# Microcontroller.net
KiCad netlist of a schematic drawn in Altium Designer
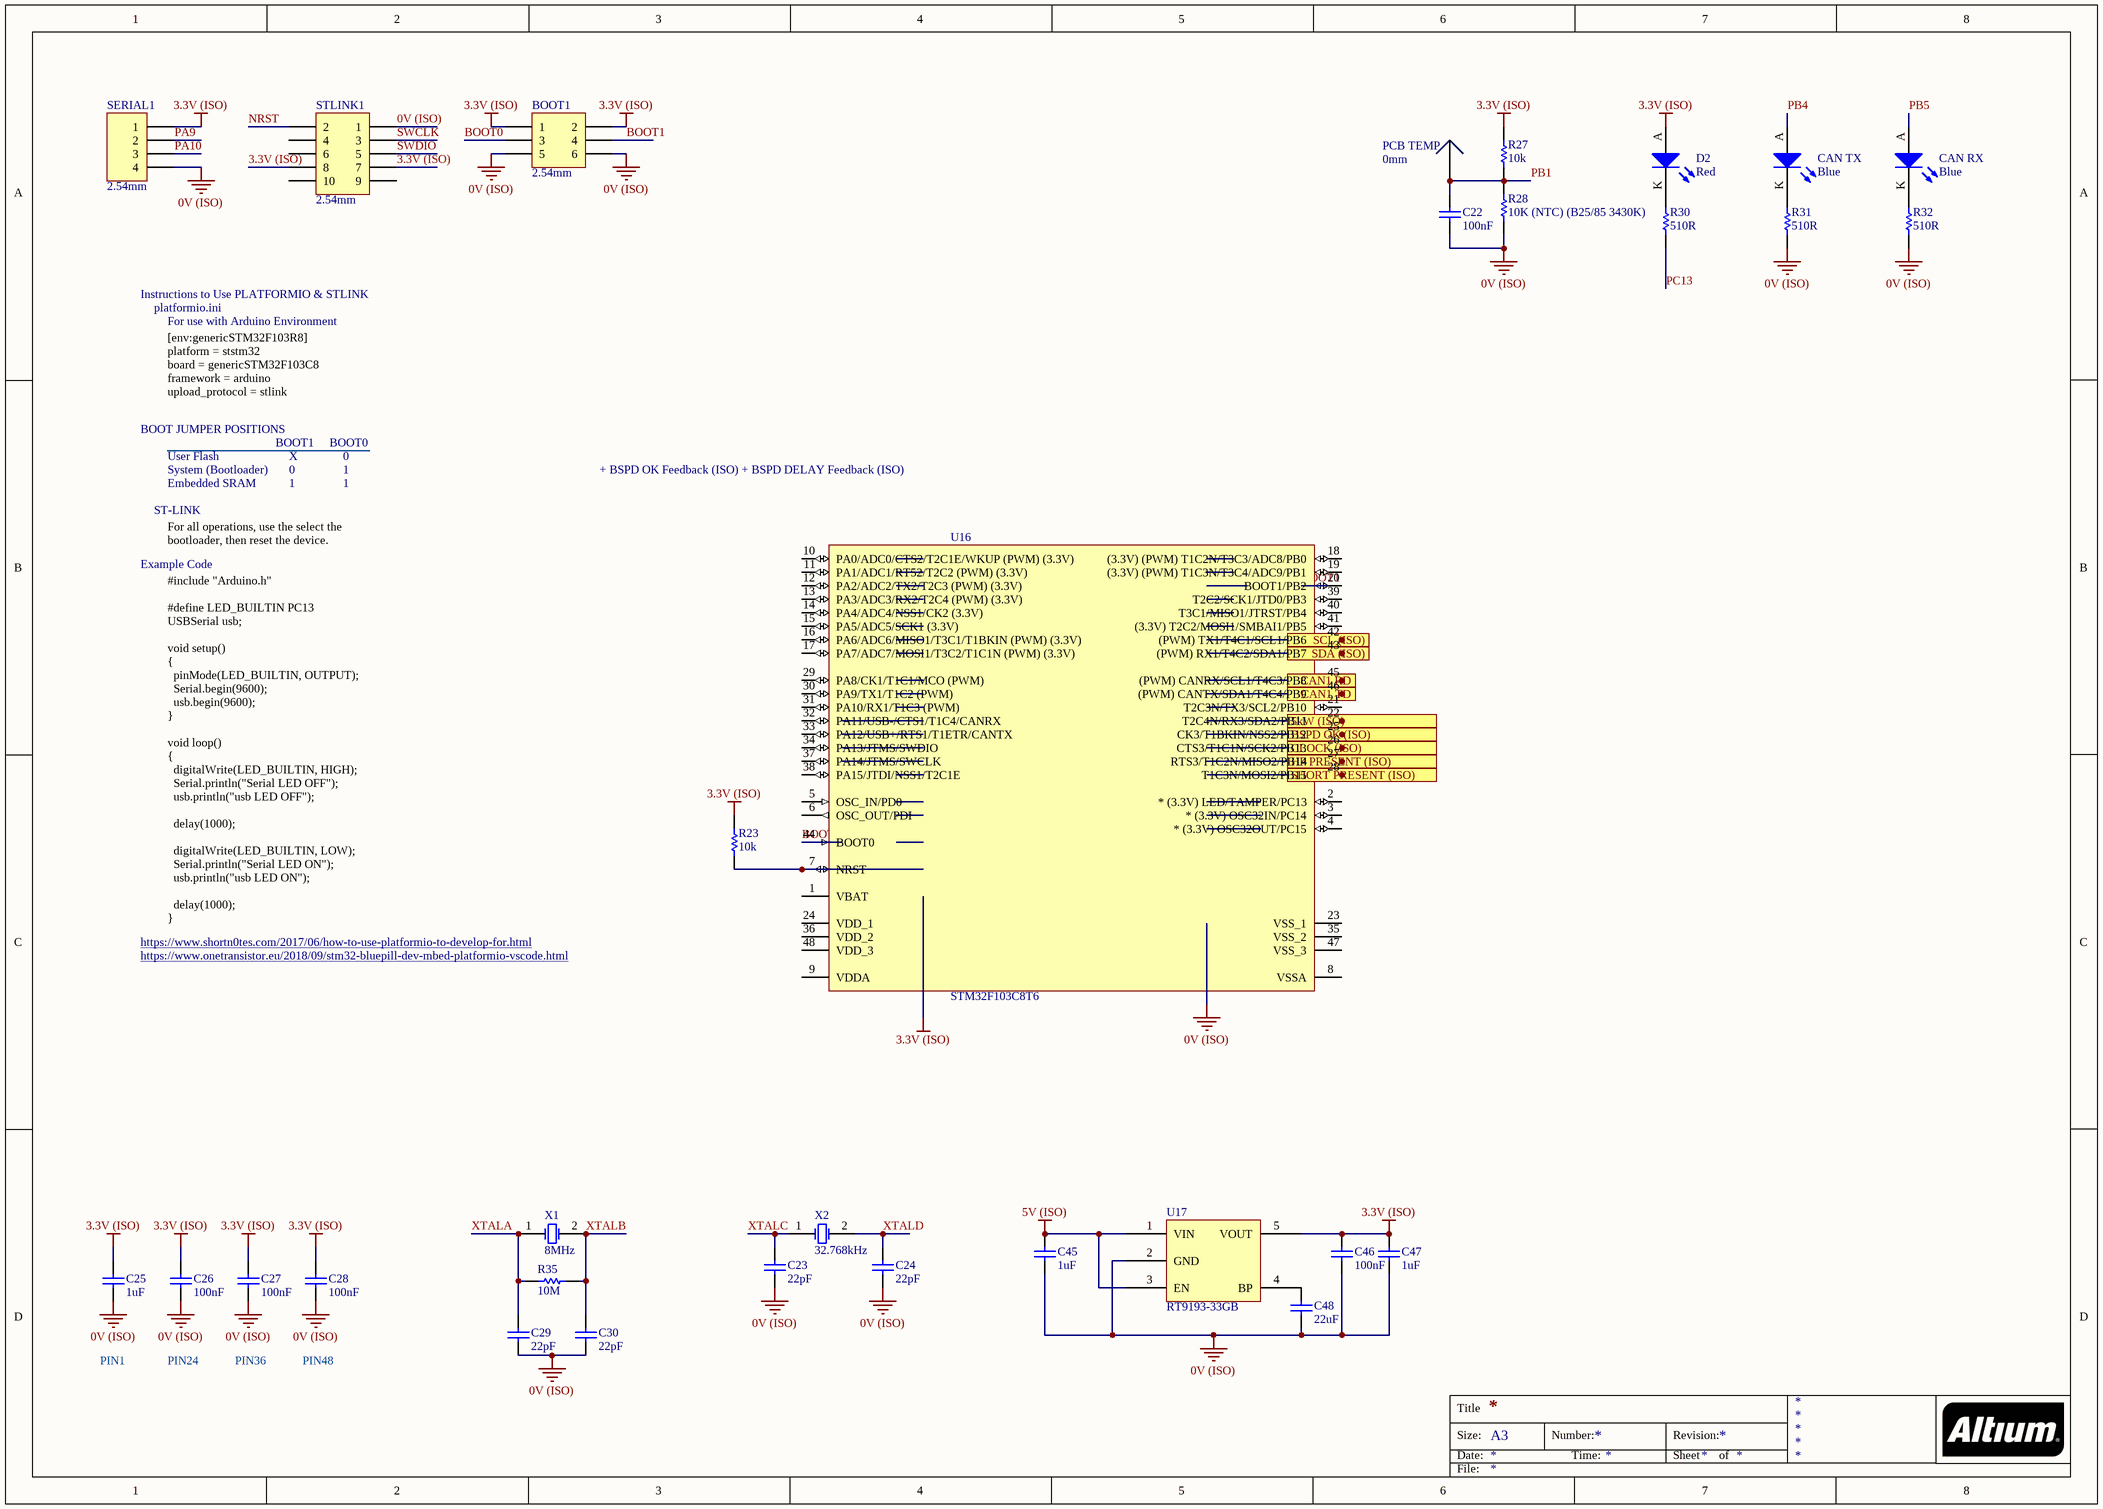
[diagram p0: Microcontroller.SchDoc]

(export (version "E")
  (design (tool "Eeschema 10.0.6"))
  (components
    (comp (ref "BOOT1")
      (value "2.54mm")
      (footprint "TH 2.54mm Header 2x3")
      (fields (field (name "PART NUMBER") "TH 2.54mm Header 2x3") (field (name "CONTACT") "NA"))
      (libsource (lib "ts_20-standard-connectors") (part "Header 2x3"))
    )
    (comp (ref "C22")
      (value "100nF")
      (footprint "0805")
      (fields
        (field (name "PART NUMBER") "GCM21BR71E104KA37L")
        (field (name "TOLERANCE") "10%")
        (field (name "MANUFACTURER") "muRata")
      )
      (libsource (lib "ts_20-standard-library") (part "Capacitor"))
    )
    (comp (ref "C23")
      (value "22pF")
      (footprint "0805")
      (fields
        (field (name "PART NUMBER") "GCM21B5C1H220JA37L")
        (field (name "TOLERANCE") "5%")
        (field (name "MANUFACTURER") "muRata")
      )
      (libsource (lib "ts_20-standard-library") (part "Capacitor"))
    )
    (comp (ref "C24")
      (value "22pF")
      (footprint "0805")
      (fields
        (field (name "PART NUMBER") "GCM21B5C1H220JA37L")
        (field (name "TOLERANCE") "5%")
        (field (name "MANUFACTURER") "muRata")
      )
      (libsource (lib "ts_20-standard-library") (part "Capacitor"))
    )
    (comp (ref "C25")
      (value "1uF")
      (footprint "0805")
      (fields
        (field (name "PART NUMBER") "AC0805KKX7R8BB105")
        (field (name "TOLERANCE") "10%")
        (field (name "MANUFACTURER") "YAGEO")
      )
      (libsource (lib "ts_20-standard-library") (part "Capacitor"))
    )
    (comp (ref "C26")
      (value "100nF")
      (footprint "0805")
      (fields
        (field (name "PART NUMBER") "GCM21BR71E104KA37L")
        (field (name "TOLERANCE") "10%")
        (field (name "MANUFACTURER") "muRata")
      )
      (libsource (lib "ts_20-standard-library") (part "Capacitor"))
    )
    (comp (ref "C27")
      (value "100nF")
      (footprint "0805")
      (fields
        (field (name "PART NUMBER") "GCM21BR71E104KA37L")
        (field (name "TOLERANCE") "10%")
        (field (name "MANUFACTURER") "muRata")
      )
      (libsource (lib "ts_20-standard-library") (part "Capacitor"))
    )
    (comp (ref "C28")
      (value "100nF")
      (footprint "0805")
      (fields
        (field (name "PART NUMBER") "GCM21BR71E104KA37L")
        (field (name "TOLERANCE") "10%")
        (field (name "MANUFACTURER") "muRata")
      )
      (libsource (lib "ts_20-standard-library") (part "Capacitor"))
    )
    (comp (ref "C29")
      (value "22pF")
      (footprint "0805")
      (fields
        (field (name "PART NUMBER") "GCM21B5C1H220JA37L")
        (field (name "TOLERANCE") "5%")
        (field (name "MANUFACTURER") "muRata")
      )
      (libsource (lib "ts_20-standard-library") (part "Capacitor"))
    )
    (comp (ref "C30")
      (value "22pF")
      (footprint "0805")
      (fields
        (field (name "PART NUMBER") "GCM21B5C1H220JA37L")
        (field (name "TOLERANCE") "5%")
        (field (name "MANUFACTURER") "muRata")
      )
      (libsource (lib "ts_20-standard-library") (part "Capacitor"))
    )
    (comp (ref "C45")
      (value "1uF")
      (footprint "0805")
      (fields
        (field (name "PART NUMBER") "GCM21BR71A105KA37L")
        (field (name "TOLERANCE") "10%")
        (field (name "MANUFACTURER") "muRata")
      )
      (libsource (lib "ts_20-standard-library") (part "Capacitor"))
    )
    (comp (ref "C46")
      (value "100nF")
      (footprint "0805")
      (fields
        (field (name "PART NUMBER") "GCM21BR71E104KA37L")
        (field (name "TOLERANCE") "10%")
        (field (name "MANUFACTURER") "muRata")
      )
      (libsource (lib "ts_20-standard-library") (part "Capacitor"))
    )
    (comp (ref "C47")
      (value "1uF")
      (footprint "0805")
      (fields
        (field (name "PART NUMBER") "GCM21BR71A105KA37L")
        (field (name "TOLERANCE") "10%")
        (field (name "MANUFACTURER") "muRata")
      )
      (libsource (lib "ts_20-standard-library") (part "Capacitor"))
    )
    (comp (ref "C48")
      (value "22uF")
      (footprint "0805")
      (fields
        (field (name "PART NUMBER") "GRM21BR61A226ME51L")
        (field (name "TOLERANCE") "20%")
        (field (name "MANUFACTURER") "muRata")
      )
      (libsource (lib "ts_20-standard-library") (part "Capacitor"))
    )
    (comp (ref "CAN RX")
      (value "Blue")
      (footprint "0805 LED")
      (description "LED BLUE CLEAR 2012 SMD")
      (fields
        (field (name "PART NUMBER") "SML-MN2BCTT86C")
        (field (name "MANUFACTURER") "ROHM Semiconductor")
      )
      (libsource (lib "ts_20-standard-library") (part "LED"))
    )
    (comp (ref "CAN TX")
      (value "Blue")
      (footprint "0805 LED")
      (description "LED BLUE CLEAR 2012 SMD")
      (fields
        (field (name "PART NUMBER") "SML-MN2BCTT86C")
        (field (name "MANUFACTURER") "ROHM Semiconductor")
      )
      (libsource (lib "ts_20-standard-library") (part "LED"))
    )
    (comp (ref "D2")
      (value "Red")
      (footprint "0805 LED")
      (description "Red LED Indication - Discrete 1.75V 0805 (2012 Metric)")
      (fields (field (name "PART NUMBER") "SML-210LTT86") (field (name "MANUFACTURER") "ROHM Semiconductor"))
      (libsource (lib "ts_20-standard-library") (part "LED"))
    )
    (comp (ref "PCB TEMP")
      (value "0mm")
      (footprint "SMD Test Point")
      (fields (field (name "PART NUMBER") "SMD Test Point") (field (name "CONTACT") "NA"))
      (libsource (lib "ts_20-standard-connectors") (part "Test Point"))
    )
    (comp (ref "R23")
      (value "10k")
      (footprint "0805")
      (fields
        (field (name "MANUFACTURER") "YAGEO")
        (field (name "PART NUMBER") "RC0805FR0710KL")
        (field (name "TOLERANCE") "0.01")
      )
      (libsource (lib "ts_20-standard-library") (part "Resistor"))
    )
    (comp (ref "R27")
      (value "10k")
      (footprint "0805")
      (fields
        (field (name "PART NUMBER") "RC0805FR0710KL")
        (field (name "MANUFACTURER") "YAGEO")
        (field (name "TOLERANCE") "0.01")
      )
      (libsource (lib "ts_20-standard-library") (part "Resistor"))
    )
    (comp (ref "R28")
      (value "10K (NTC) (B25/85 3430K)")
      (footprint "0805")
      (fields
        (field (name "PART NUMBER") "NTCS0805E3103FLT")
        (field (name "MANUFACTURER") "Vishay Beyschlag")
        (field (name "TOLERANCE") "0.01")
      )
      (libsource (lib "ts_20-standard-library") (part "Resistor"))
    )
    (comp (ref "R30")
      (value "510R")
      (footprint "0805")
      (fields
        (field (name "PART NUMBER") "RC0805FR07510RL")
        (field (name "MANUFACTURER") "YAGEO")
        (field (name "TOLERANCE") "0.01")
      )
      (libsource (lib "ts_20-standard-library") (part "Resistor"))
    )
    (comp (ref "R31")
      (value "510R")
      (footprint "0805")
      (fields
        (field (name "PART NUMBER") "RC0805FR07510RL")
        (field (name "MANUFACTURER") "YAGEO")
        (field (name "TOLERANCE") "0.01")
      )
      (libsource (lib "ts_20-standard-library") (part "Resistor"))
    )
    (comp (ref "R32")
      (value "510R")
      (footprint "0805")
      (fields
        (field (name "PART NUMBER") "RC0805FR07510RL")
        (field (name "MANUFACTURER") "YAGEO")
        (field (name "TOLERANCE") "0.01")
      )
      (libsource (lib "ts_20-standard-library") (part "Resistor"))
    )
    (comp (ref "R33")
      (value "10k")
      (footprint "0805")
      (fields
        (field (name "PART NUMBER") "RC0805FR0710KL")
        (field (name "MANUFACTURER") "YAGEO")
        (field (name "TOLERANCE") "0.01")
      )
      (libsource (lib "ts_20-standard-library") (part "Resistor"))
    )
    (comp (ref "R34")
      (value "10k")
      (footprint "0805")
      (fields
        (field (name "PART NUMBER") "RC0805FR0710KL")
        (field (name "MANUFACTURER") "YAGEO")
        (field (name "TOLERANCE") "0.01")
      )
      (libsource (lib "ts_20-standard-library") (part "Resistor"))
    )
    (comp (ref "R35")
      (value "10M")
      (footprint "0805")
      (fields
        (field (name "PART NUMBER") "RC0805FR0710ML")
        (field (name "MANUFACTURER") "YAGEO")
        (field (name "TOLERANCE") "0.01")
      )
      (libsource (lib "ts_20-standard-library") (part "Resistor"))
    )
    (comp (ref "SERIAL1")
      (value "2.54mm")
      (footprint "TH 2.54mm Header 1x4")
      (fields (field (name "PART NUMBER") "TH 2.54mm Header 1x4") (field (name "CONTACT") "NA"))
      (libsource (lib "ts_20-standard-connectors") (part "Header 1x4"))
    )
    (comp (ref "STLINK1")
      (value "2.54mm")
      (footprint "TH 2.54mm Header 2x5")
      (fields (field (name "PART NUMBER") "TH 2.54mm Header 2x5") (field (name "CONTACT") "NA"))
      (libsource (lib "ts_20-standard-connectors") (part "Header 2x5"))
    )
    (comp (ref "U16")
      (value "STM32F103C8T6")
      (footprint "STM 48-LQFP")
      (description "ARM® Cortex®-M3 STM32F1 Microcontroller IC 32-Bit 72MHz 64KB (64K x 8) FLASH")
      (fields
        (field (name "MANUFACTURER") "STMicroelectronics")
        (field (name "DIGIKEY PART NUMBER") "497-6063-ND")
      )
      (libsource (lib "ts_20-standard-library") (part "STM32F103C8T6"))
    )
    (comp (ref "U17")
      (value "RT9193-33GB")
      (footprint "RICHTEK SOT-23-5")
      (description "IC REG LINEAR 3.3V 300MA SOT23-5")
      (fields (field (name "MANUFACTURER") "Richtek") (field (name "DIGIKEY PART NUMBER") "1028-1014-1-ND"))
      (libsource (lib "ts_20-standard-library") (part "RT9193-33GB"))
    )
    (comp (ref "X1")
      (value "8MHz")
      (footprint "Abracon HC-49/US")
      (fields
        (field (name "PART NUMBER") "ABLS-8.000MHZ-B4-T")
        (field (name "MANUFACTURER") "Abracon LLC")
        (field (name "DIGIKEY PART NUMBER") "535-10212-2-ND")
      )
      (libsource (lib "ts_20-standard-library") (part "Crystal"))
    )
    (comp (ref "X2")
      (value "32.768kHz")
      (footprint "EPSON 2-SMD")
      (fields
        (field (name "PART NUMBER") "FC-135 32.7680KA-A5")
        (field (name "MANUFACTURER") "EPSON")
        (field (name "DIGIKEY PART NUMBER") "SER4103TR-ND")
      )
      (libsource (lib "ts_20-standard-library") (part "Crystal"))
    )
  )
  (nets
    (net (code "1") (name "/BOOT0") (class "Default")
      (node (ref "BOOT1") (pin "3") (pinfunction "3_3") (pintype "passive"))
      (node (ref "R34") (pin "1") (pinfunction "1_1") (pintype "passive"))
      (node (ref "U16") (pin "44") (pinfunction "BOOT0_44") (pintype "input"))
    )
    (net (code "2") (name "/BOOT1") (class "Default")
      (node (ref "BOOT1") (pin "4") (pinfunction "4_4") (pintype "passive"))
      (node (ref "R33") (pin "2") (pinfunction "2_2") (pintype "passive"))
    )
    (net (code "3") (name "/NRST") (class "Default")
      (node (ref "R23") (pin "1") (pinfunction "1_1") (pintype "passive"))
      (node (ref "STLINK1") (pin "2") (pinfunction "2_2") (pintype "passive"))
      (node (ref "U16") (pin "7") (pinfunction "NRST_7") (pintype "bidirectional"))
    )
    (net (code "13") (name "/PA9") (class "Default")
      (node (ref "SERIAL1") (pin "2") (pinfunction "2_2") (pintype "passive"))
    )
    (net (code "14") (name "/PA10") (class "Default")
      (node (ref "SERIAL1") (pin "3") (pinfunction "3_3") (pintype "passive"))
    )
    (net (code "17") (name "/PB1") (class "Default")
      (node (ref "C22") (pin "2") (pinfunction "2_2") (pintype "passive"))
      (node (ref "PCB TEMP") (pin "1") (pinfunction "1_1") (pintype "passive"))
      (node (ref "R27") (pin "1") (pinfunction "1_1") (pintype "passive"))
      (node (ref "R28") (pin "2") (pinfunction "2_2") (pintype "passive"))
    )
    (net (code "19") (name "/PB4") (class "Default")
      (node (ref "CAN TX") (pin "A") (pinfunction "A_A") (pintype "passive"))
    )
    (net (code "20") (name "/PB5") (class "Default")
      (node (ref "CAN RX") (pin "A") (pinfunction "A_A") (pintype "passive"))
    )
    (net (code "31") (name "/PC13") (class "Default")
      (node (ref "R30") (pin "1") (pinfunction "1_1") (pintype "passive"))
    )
    (net (code "32") (name "/SWCLK") (class "Default")
      (node (ref "STLINK1") (pin "3") (pinfunction "3_3") (pintype "passive"))
    )
    (net (code "33") (name "/SWDIO") (class "Default")
      (node (ref "STLINK1") (pin "5") (pinfunction "5_5") (pintype "passive"))
    )
    (net (code "36") (name "/XTALA") (class "Default")
      (node (ref "C29") (pin "2") (pinfunction "2_2") (pintype "passive"))
      (node (ref "R35") (pin "1") (pinfunction "1_1") (pintype "passive"))
      (node (ref "X1") (pin "1") (pinfunction "OSC1_1") (pintype "passive"))
    )
    (net (code "37") (name "/XTALB") (class "Default")
      (node (ref "C30") (pin "2") (pinfunction "2_2") (pintype "passive"))
      (node (ref "R35") (pin "2") (pinfunction "2_2") (pintype "passive"))
      (node (ref "X1") (pin "2") (pinfunction "OSC2_2") (pintype "passive"))
    )
    (net (code "38") (name "/XTALC") (class "Default")
      (node (ref "C23") (pin "2") (pinfunction "2_2") (pintype "passive"))
      (node (ref "X2") (pin "1") (pinfunction "OSC1_1") (pintype "passive"))
    )
    (net (code "39") (name "/XTALD") (class "Default")
      (node (ref "C24") (pin "2") (pinfunction "2_2") (pintype "passive"))
      (node (ref "X2") (pin "2") (pinfunction "OSC2_2") (pintype "passive"))
    )
    (net (code "40") (name "0V (ISO)") (class "Default")
      (node (ref "BOOT1") (pin "5") (pinfunction "5_5") (pintype "passive"))
      (node (ref "BOOT1") (pin "6") (pinfunction "6_6") (pintype "passive"))
      (node (ref "C22") (pin "1") (pinfunction "1_1") (pintype "passive"))
      (node (ref "C23") (pin "1") (pinfunction "1_1") (pintype "passive"))
      (node (ref "C24") (pin "1") (pinfunction "1_1") (pintype "passive"))
      (node (ref "C25") (pin "1") (pinfunction "1_1") (pintype "passive"))
      (node (ref "C26") (pin "1") (pinfunction "1_1") (pintype "passive"))
      (node (ref "C27") (pin "1") (pinfunction "1_1") (pintype "passive"))
      (node (ref "C28") (pin "1") (pinfunction "1_1") (pintype "passive"))
      (node (ref "C29") (pin "1") (pinfunction "1_1") (pintype "passive"))
      (node (ref "C30") (pin "1") (pinfunction "1_1") (pintype "passive"))
      (node (ref "C45") (pin "1") (pinfunction "1_1") (pintype "passive"))
      (node (ref "C46") (pin "1") (pinfunction "1_1") (pintype "passive"))
      (node (ref "C47") (pin "1") (pinfunction "1_1") (pintype "passive"))
      (node (ref "C48") (pin "1") (pinfunction "1_1") (pintype "passive"))
      (node (ref "R28") (pin "1") (pinfunction "1_1") (pintype "passive"))
      (node (ref "R31") (pin "1") (pinfunction "1_1") (pintype "passive"))
      (node (ref "R32") (pin "1") (pinfunction "1_1") (pintype "passive"))
      (node (ref "SERIAL1") (pin "4") (pinfunction "4_4") (pintype "passive"))
      (node (ref "STLINK1") (pin "1") (pinfunction "1_1") (pintype "passive"))
      (node (ref "U17") (pin "2") (pinfunction "GND_2") (pintype "passive"))
    )
    (net (code "41") (name "3.3V (ISO)") (class "Default")
      (node (ref "BOOT1") (pin "1") (pinfunction "1_1") (pintype "passive"))
      (node (ref "BOOT1") (pin "2") (pinfunction "2_2") (pintype "passive"))
      (node (ref "C25") (pin "2") (pinfunction "2_2") (pintype "passive"))
      (node (ref "C26") (pin "2") (pinfunction "2_2") (pintype "passive"))
      (node (ref "C27") (pin "2") (pinfunction "2_2") (pintype "passive"))
      (node (ref "C28") (pin "2") (pinfunction "2_2") (pintype "passive"))
      (node (ref "C46") (pin "2") (pinfunction "2_2") (pintype "passive"))
      (node (ref "C47") (pin "2") (pinfunction "2_2") (pintype "passive"))
      (node (ref "D2") (pin "A") (pinfunction "A_A") (pintype "passive"))
      (node (ref "R23") (pin "2") (pinfunction "2_2") (pintype "passive"))
      (node (ref "R27") (pin "2") (pinfunction "2_2") (pintype "passive"))
      (node (ref "SERIAL1") (pin "1") (pinfunction "1_1") (pintype "passive"))
      (node (ref "STLINK1") (pin "7") (pinfunction "7_7") (pintype "passive"))
      (node (ref "STLINK1") (pin "8") (pinfunction "8_8") (pintype "passive"))
      (node (ref "U17") (pin "5") (pinfunction "VOUT_5") (pintype "passive"))
    )
    (net (code "42") (name "5V (ISO)") (class "Default")
      (node (ref "C45") (pin "2") (pinfunction "2_2") (pintype "passive"))
      (node (ref "U17") (pin "1") (pinfunction "VIN_1") (pintype "passive"))
      (node (ref "U17") (pin "3") (pinfunction "EN_3") (pintype "passive"))
    )
    (net (code "43") (name "Net-(CAN RX-PadK)") (class "Default")
      (node (ref "CAN RX") (pin "K") (pinfunction "K_K") (pintype "passive"))
      (node (ref "R32") (pin "2") (pinfunction "2_2") (pintype "passive"))
    )
    (net (code "44") (name "Net-(CAN TX-PadK)") (class "Default")
      (node (ref "CAN TX") (pin "K") (pinfunction "K_K") (pintype "passive"))
      (node (ref "R31") (pin "2") (pinfunction "2_2") (pintype "passive"))
    )
    (net (code "45") (name "Net-(D2-PadK)") (class "Default")
      (node (ref "D2") (pin "K") (pinfunction "K_K") (pintype "passive"))
      (node (ref "R30") (pin "2") (pinfunction "2_2") (pintype "passive"))
    )
    (net (code "46") (name "Net-(U17-BP)") (class "Default")
      (node (ref "C48") (pin "2") (pinfunction "2_2") (pintype "passive"))
      (node (ref "U17") (pin "4") (pinfunction "BP_4") (pintype "passive"))
    )
    (net (code "47") (name "unconnected-(R33-Pad1)") (class "Default")
      (node (ref "R33") (pin "1") (pinfunction "1_1") (pintype "passive"))
    )
    (net (code "48") (name "unconnected-(R34-Pad2)") (class "Default")
      (node (ref "R34") (pin "2") (pinfunction "2_2") (pintype "passive"))
    )
    (net (code "49") (name "unconnected-(STLINK1-Pad4)") (class "Default")
      (node (ref "STLINK1") (pin "4") (pinfunction "4_4") (pintype "passive"))
    )
    (net (code "50") (name "unconnected-(STLINK1-Pad6)") (class "Default")
      (node (ref "STLINK1") (pin "6") (pinfunction "6_6") (pintype "passive"))
    )
    (net (code "51") (name "unconnected-(STLINK1-Pad9)") (class "Default")
      (node (ref "STLINK1") (pin "9") (pinfunction "9_9") (pintype "passive"))
    )
    (net (code "52") (name "unconnected-(STLINK1-Pad10)") (class "Default")
      (node (ref "STLINK1") (pin "10") (pinfunction "10_10") (pintype "passive"))
    )
    (net (code "53") (name "unconnected-(U16-(3.3V)_(PWM)_T1C2N{slash}T3C3{slash}ADC8{slash}PB0-Pad18)") (class "Default")
      (node (ref "U16") (pin "18") (pinfunction "(3.3V)_(PWM)_T1C2N/T3C3/ADC8/PB0_18") (pintype "bidirectional"))
    )
    (net (code "54") (name "unconnected-(U16-(3.3V)_(PWM)_T1C3N{slash}T3C4{slash}ADC9{slash}PB1-Pad19)") (class "Default")
      (node (ref "U16") (pin "19") (pinfunction "(3.3V)_(PWM)_T1C3N/T3C4/ADC9/PB1_19") (pintype "bidirectional"))
    )
    (net (code "55") (name "unconnected-(U16-(3.3V)_T2C2{slash}MOSI1{slash}SMBAI1{slash}PB5-Pad41)") (class "Default")
      (node (ref "U16") (pin "41") (pinfunction "(3.3V)_T2C2/MOSI1/SMBAI1/PB5_41") (pintype "bidirectional"))
    )
    (net (code "56") (name "unconnected-(U16-(PWM)_CANRX{slash}SCL1{slash}T4C3{slash}PB8-Pad45)") (class "Default")
      (node (ref "U16") (pin "45") (pinfunction "(PWM)_CANRX/SCL1/T4C3/PB8_45") (pintype "bidirectional"))
    )
    (net (code "57") (name "unconnected-(U16-(PWM)_CANTX{slash}SDA1{slash}T4C4{slash}PB9-Pad46)") (class "Default")
      (node (ref "U16") (pin "46") (pinfunction "(PWM)_CANTX/SDA1/T4C4/PB9_46") (pintype "bidirectional"))
    )
    (net (code "58") (name "unconnected-(U16-(PWM)_RX1{slash}T4C2{slash}SDA1{slash}PB7-Pad43)") (class "Default")
      (node (ref "U16") (pin "43") (pinfunction "(PWM)_RX1/T4C2/SDA1/PB7_43") (pintype "bidirectional"))
    )
    (net (code "59") (name "unconnected-(U16-(PWM)_TX1{slash}T4C1{slash}SCL1{slash}PB6-Pad42)") (class "Default")
      (node (ref "U16") (pin "42") (pinfunction "(PWM)_TX1/T4C1/SCL1/PB6_42") (pintype "bidirectional"))
    )
    (net (code "60") (name "unconnected-(U16-*_(3.3V)_LED{slash}TAMPER{slash}PC13-Pad2)") (class "Default")
      (node (ref "U16") (pin "2") (pinfunction "*_(3.3V)_LED/TAMPER/PC13_2") (pintype "bidirectional"))
    )
    (net (code "61") (name "unconnected-(U16-*_(3.3V)_OSC32IN{slash}PC14-Pad3)") (class "Default")
      (node (ref "U16") (pin "3") (pinfunction "*_(3.3V)_OSC32IN/PC14_3") (pintype "bidirectional"))
    )
    (net (code "62") (name "unconnected-(U16-*_(3.3V)_OSC32OUT{slash}PC15-Pad4)") (class "Default")
      (node (ref "U16") (pin "4") (pinfunction "*_(3.3V)_OSC32OUT/PC15_4") (pintype "bidirectional"))
    )
    (net (code "63") (name "unconnected-(U16-BOOT1{slash}PB2-Pad20)") (class "Default")
      (node (ref "U16") (pin "20") (pinfunction "BOOT1/PB2_20") (pintype "bidirectional"))
    )
    (net (code "64") (name "unconnected-(U16-CK3{slash}T1BKIN{slash}NSS2{slash}PB12-Pad25)") (class "Default")
      (node (ref "U16") (pin "25") (pinfunction "CK3/T1BKIN/NSS2/PB12_25") (pintype "bidirectional"))
    )
    (net (code "65") (name "unconnected-(U16-CTS3{slash}T1C1N{slash}SCK2{slash}PB13-Pad26)") (class "Default")
      (node (ref "U16") (pin "26") (pinfunction "CTS3/T1C1N/SCK2/PB13_26") (pintype "bidirectional"))
    )
    (net (code "66") (name "unconnected-(U16-OSC_IN{slash}PD0-Pad5)") (class "Default")
      (node (ref "U16") (pin "5") (pinfunction "OSC_IN/PD0_5") (pintype "input"))
    )
    (net (code "67") (name "unconnected-(U16-OSC_OUT{slash}PDI-Pad6)") (class "Default")
      (node (ref "U16") (pin "6") (pinfunction "OSC_OUT/PDI_6") (pintype "output"))
    )
    (net (code "68") (name "unconnected-(U16-PA0{slash}ADC0{slash}CTS2{slash}T2C1E{slash}WKUP_(PWM)_(3.3V)-Pad10)") (class "Default")
      (node (ref "U16") (pin "10") (pinfunction "PA0/ADC0/CTS2/T2C1E/WKUP_(PWM)_(3.3V)_10") (pintype "bidirectional"))
    )
    (net (code "69") (name "unconnected-(U16-PA1{slash}ADC1{slash}RT52{slash}T2C2_(PWM)_(3.3V)-Pad11)") (class "Default")
      (node (ref "U16") (pin "11") (pinfunction "PA1/ADC1/RT52/T2C2_(PWM)_(3.3V)_11") (pintype "bidirectional"))
    )
    (net (code "70") (name "unconnected-(U16-PA2{slash}ADC2{slash}TX2{slash}T2C3_(PWM)_(3.3V)-Pad12)") (class "Default")
      (node (ref "U16") (pin "12") (pinfunction "PA2/ADC2/TX2/T2C3_(PWM)_(3.3V)_12") (pintype "bidirectional"))
    )
    (net (code "71") (name "unconnected-(U16-PA3{slash}ADC3{slash}RX2{slash}T2C4_(PWM)_(3.3V)-Pad13)") (class "Default")
      (node (ref "U16") (pin "13") (pinfunction "PA3/ADC3/RX2/T2C4_(PWM)_(3.3V)_13") (pintype "bidirectional"))
    )
    (net (code "72") (name "unconnected-(U16-PA4{slash}ADC4{slash}NSS1{slash}CK2_(3.3V)-Pad14)") (class "Default")
      (node (ref "U16") (pin "14") (pinfunction "PA4/ADC4/NSS1/CK2_(3.3V)_14") (pintype "bidirectional"))
    )
    (net (code "73") (name "unconnected-(U16-PA5{slash}ADC5{slash}SCK1_(3.3V)-Pad15)") (class "Default")
      (node (ref "U16") (pin "15") (pinfunction "PA5/ADC5/SCK1_(3.3V)_15") (pintype "bidirectional"))
    )
    (net (code "74") (name "unconnected-(U16-PA6{slash}ADC6{slash}MISO1{slash}T3C1{slash}T1BKIN_(PWM)_(3.3V)-Pad16)") (class "Default")
      (node (ref "U16") (pin "16") (pinfunction "PA6/ADC6/MISO1/T3C1/T1BKIN_(PWM)_(3.3V)_16") (pintype "bidirectional"))
    )
    (net (code "75") (name "unconnected-(U16-PA7{slash}ADC7{slash}MOSI1{slash}T3C2{slash}T1C1N_(PWM)_(3.3V)-Pad17)") (class "Default")
      (node (ref "U16") (pin "17") (pinfunction "PA7/ADC7/MOSI1/T3C2/T1C1N_(PWM)_(3.3V)_17") (pintype "bidirectional"))
    )
    (net (code "76") (name "unconnected-(U16-PA8{slash}CK1{slash}T1C1{slash}MCO_(PWM)-Pad29)") (class "Default")
      (node (ref "U16") (pin "29") (pinfunction "PA8/CK1/T1C1/MCO_(PWM)_29") (pintype "bidirectional"))
    )
    (net (code "77") (name "unconnected-(U16-PA9{slash}TX1{slash}T1C2_(PWM)-Pad30)") (class "Default")
      (node (ref "U16") (pin "30") (pinfunction "PA9/TX1/T1C2_(PWM)_30") (pintype "bidirectional"))
    )
    (net (code "78") (name "unconnected-(U16-PA10{slash}RX1{slash}T1C3_(PWM)-Pad31)") (class "Default")
      (node (ref "U16") (pin "31") (pinfunction "PA10/RX1/T1C3_(PWM)_31") (pintype "bidirectional"))
    )
    (net (code "79") (name "unconnected-(U16-PA11{slash}USB-{slash}CTS1{slash}T1C4{slash}CANRX-Pad32)") (class "Default")
      (node (ref "U16") (pin "32") (pinfunction "PA11/USB-/CTS1/T1C4/CANRX_32") (pintype "bidirectional"))
    )
    (net (code "80") (name "unconnected-(U16-PA12{slash}USB+{slash}RTS1{slash}T1ETR{slash}CANTX-Pad33)") (class "Default")
      (node (ref "U16") (pin "33") (pinfunction "PA12/USB+/RTS1/T1ETR/CANTX_33") (pintype "bidirectional"))
    )
    (net (code "81") (name "unconnected-(U16-PA13{slash}JTMS{slash}SWDIO-Pad34)") (class "Default")
      (node (ref "U16") (pin "34") (pinfunction "PA13/JTMS/SWDIO_34") (pintype "bidirectional"))
    )
    (net (code "82") (name "unconnected-(U16-PA14{slash}JTMS{slash}SWCLK-Pad37)") (class "Default")
      (node (ref "U16") (pin "37") (pinfunction "PA14/JTMS/SWCLK_37") (pintype "bidirectional"))
    )
    (net (code "83") (name "unconnected-(U16-PA15{slash}JTDI{slash}NSS1{slash}T2C1E-Pad38)") (class "Default")
      (node (ref "U16") (pin "38") (pinfunction "PA15/JTDI/NSS1/T2C1E_38") (pintype "bidirectional"))
    )
    (net (code "84") (name "unconnected-(U16-RTS3{slash}T1C2N{slash}MISO2{slash}PB14-Pad27)") (class "Default")
      (node (ref "U16") (pin "27") (pinfunction "RTS3/T1C2N/MISO2/PB14_27") (pintype "bidirectional"))
    )
    (net (code "85") (name "unconnected-(U16-T1C3N{slash}MOSI2{slash}PB15-Pad28)") (class "Default")
      (node (ref "U16") (pin "28") (pinfunction "T1C3N/MOSI2/PB15_28") (pintype "bidirectional"))
    )
    (net (code "86") (name "unconnected-(U16-T2C2{slash}SCK1{slash}JTD0{slash}PB3-Pad39)") (class "Default")
      (node (ref "U16") (pin "39") (pinfunction "T2C2/SCK1/JTD0/PB3_39") (pintype "bidirectional"))
    )
    (net (code "87") (name "unconnected-(U16-T2C3N{slash}TX3{slash}SCL2{slash}PB10-Pad21)") (class "Default")
      (node (ref "U16") (pin "21") (pinfunction "T2C3N/TX3/SCL2/PB10_21") (pintype "bidirectional"))
    )
    (net (code "88") (name "unconnected-(U16-T2C4N{slash}RX3{slash}SDA2{slash}PB11-Pad22)") (class "Default")
      (node (ref "U16") (pin "22") (pinfunction "T2C4N/RX3/SDA2/PB11_22") (pintype "bidirectional"))
    )
    (net (code "89") (name "unconnected-(U16-T3C1{slash}MISO1{slash}JTRST{slash}PB4-Pad40)") (class "Default")
      (node (ref "U16") (pin "40") (pinfunction "T3C1/MISO1/JTRST/PB4_40") (pintype "bidirectional"))
    )
    (net (code "90") (name "unconnected-(U16-VBAT-Pad1)") (class "Default")
      (node (ref "U16") (pin "1") (pinfunction "VBAT_1") (pintype "power_in"))
    )
    (net (code "91") (name "unconnected-(U16-VDDA-Pad9)") (class "Default")
      (node (ref "U16") (pin "9") (pinfunction "VDDA_9") (pintype "power_in"))
    )
    (net (code "92") (name "unconnected-(U16-VDD_1-Pad24)") (class "Default")
      (node (ref "U16") (pin "24") (pinfunction "VDD_1_24") (pintype "power_in"))
    )
    (net (code "93") (name "unconnected-(U16-VDD_2-Pad36)") (class "Default")
      (node (ref "U16") (pin "36") (pinfunction "VDD_2_36") (pintype "power_in"))
    )
    (net (code "94") (name "unconnected-(U16-VDD_3-Pad48)") (class "Default")
      (node (ref "U16") (pin "48") (pinfunction "VDD_3_48") (pintype "power_in"))
    )
    (net (code "95") (name "unconnected-(U16-VSSA-Pad8)") (class "Default")
      (node (ref "U16") (pin "8") (pinfunction "VSSA_8") (pintype "power_in"))
    )
    (net (code "96") (name "unconnected-(U16-VSS_1-Pad23)") (class "Default")
      (node (ref "U16") (pin "23") (pinfunction "VSS_1_23") (pintype "power_in"))
    )
    (net (code "97") (name "unconnected-(U16-VSS_2-Pad35)") (class "Default")
      (node (ref "U16") (pin "35") (pinfunction "VSS_2_35") (pintype "power_in"))
    )
    (net (code "98") (name "unconnected-(U16-VSS_3-Pad47)") (class "Default")
      (node (ref "U16") (pin "47") (pinfunction "VSS_3_47") (pintype "power_in"))
    )
  )
)
